# arduino_minimal_1stk.net
KiCad netlist of a schematic drawn in EAGLE
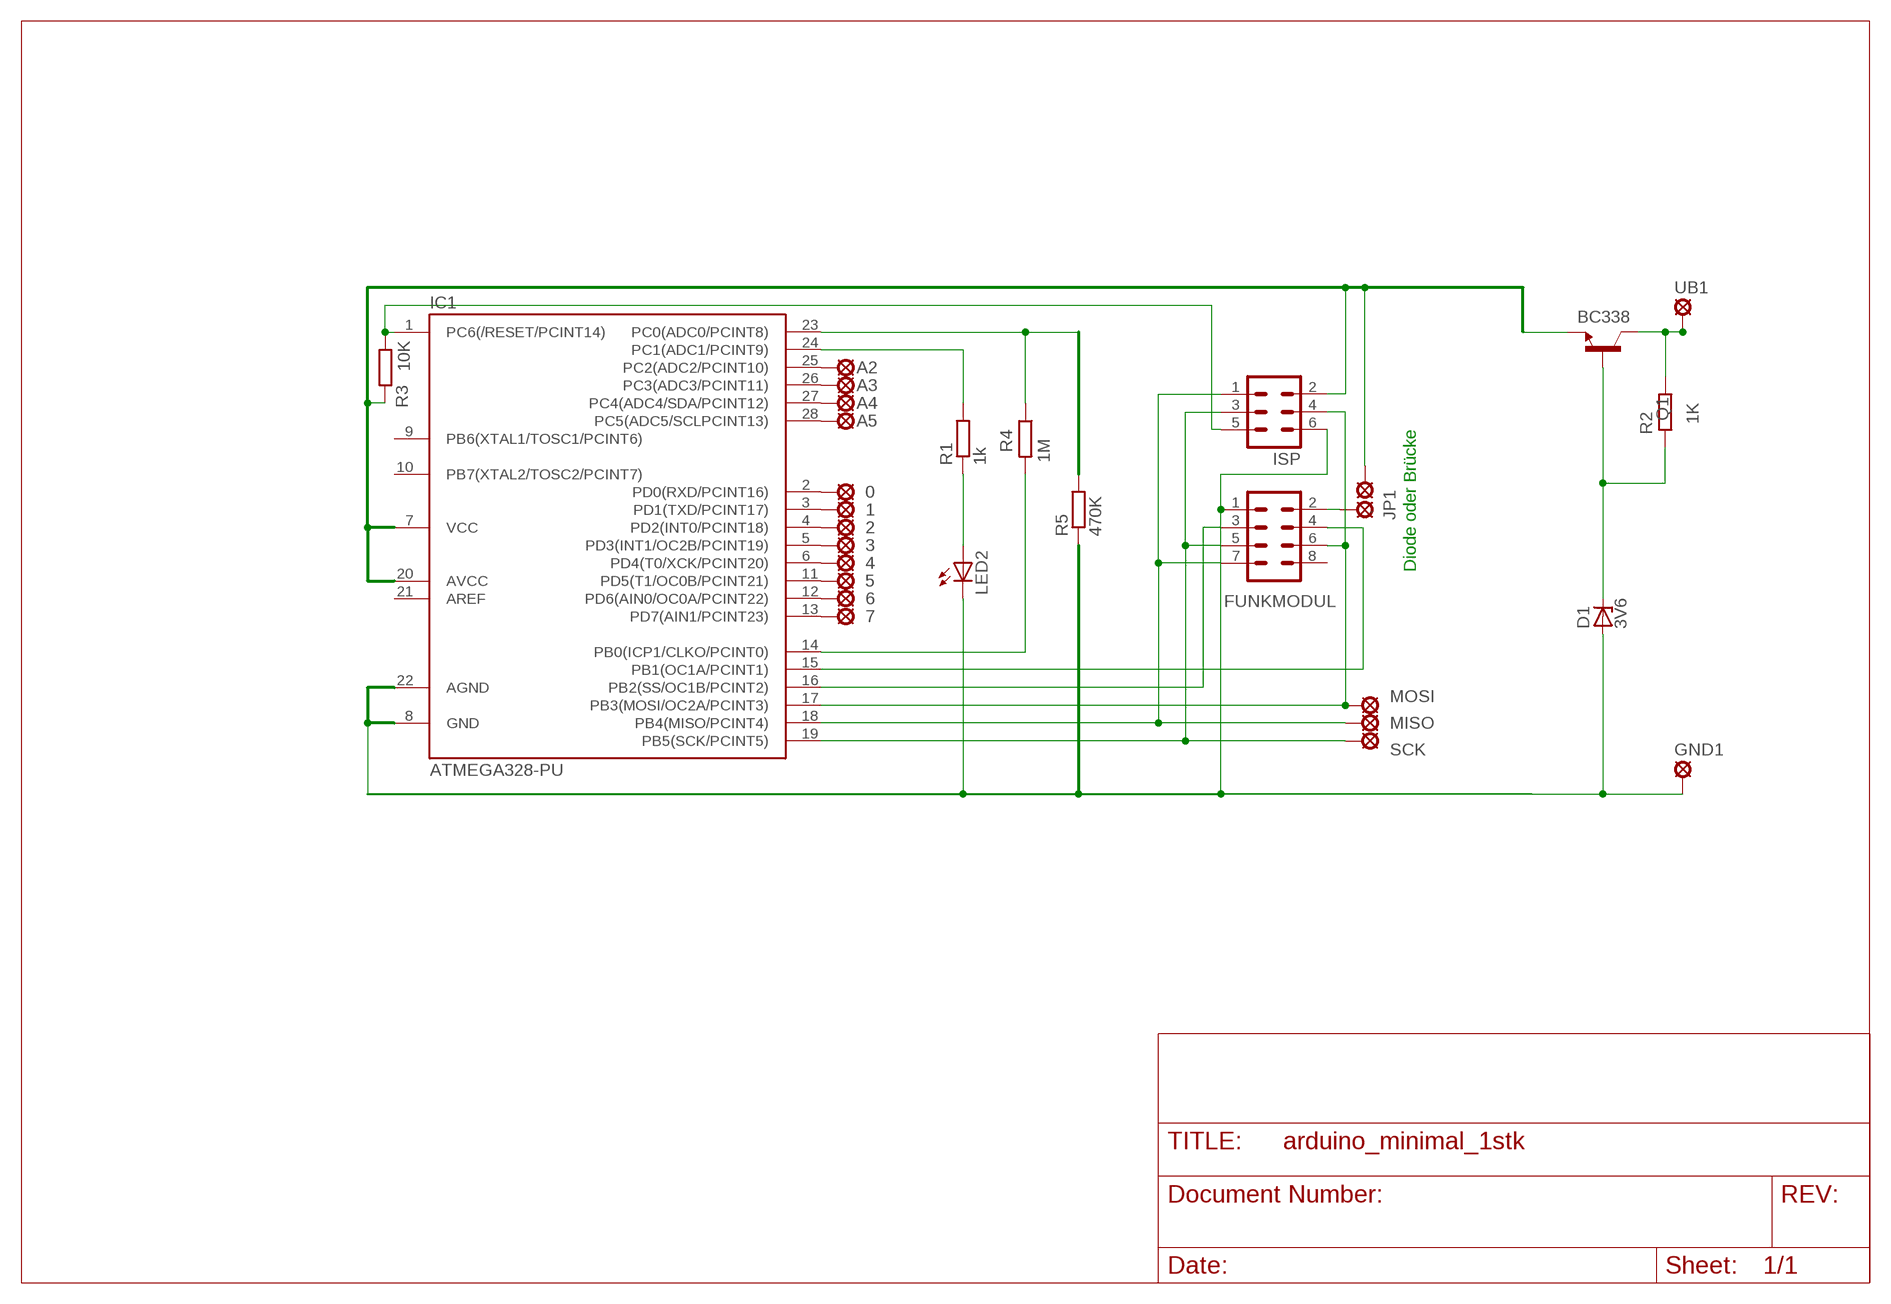
[diagram p0: schematic, sheet 1]

(export (version "E")
  (design (tool "Eeschema 10.0.6"))
  (components
    (comp (ref ".")
      (value "LSP10")
      (footprint "eagle-import:LSP10")
      (libsource (lib "eagle-import") (part "LSP10"))
    )
    (comp (ref "0")
      (value "LSP10")
      (footprint "eagle-import:LSP10")
      (libsource (lib "eagle-import") (part "LSP10"))
    )
    (comp (ref "1")
      (value "LSP10")
      (footprint "eagle-import:LSP10")
      (libsource (lib "eagle-import") (part "LSP10"))
    )
    (comp (ref "2")
      (value "LSP10")
      (footprint "eagle-import:LSP10")
      (libsource (lib "eagle-import") (part "LSP10"))
    )
    (comp (ref "3")
      (value "LSP10")
      (footprint "eagle-import:LSP10")
      (libsource (lib "eagle-import") (part "LSP10"))
    )
    (comp (ref "4")
      (value "LSP10")
      (footprint "eagle-import:LSP10")
      (libsource (lib "eagle-import") (part "LSP10"))
    )
    (comp (ref "5")
      (value "LSP10")
      (footprint "eagle-import:LSP10")
      (libsource (lib "eagle-import") (part "LSP10"))
    )
    (comp (ref "6")
      (value "LSP10")
      (footprint "eagle-import:LSP10")
      (libsource (lib "eagle-import") (part "LSP10"))
    )
    (comp (ref "7")
      (value "LSP10")
      (footprint "eagle-import:LSP10")
      (libsource (lib "eagle-import") (part "LSP10"))
    )
    (comp (ref "A2")
      (value "LSP10")
      (footprint "eagle-import:LSP10")
      (libsource (lib "eagle-import") (part "LSP10"))
    )
    (comp (ref "A3")
      (value "LSP10")
      (footprint "eagle-import:LSP10")
      (libsource (lib "eagle-import") (part "LSP10"))
    )
    (comp (ref "A4")
      (value "LSP10")
      (footprint "eagle-import:LSP10")
      (libsource (lib "eagle-import") (part "LSP10"))
    )
    (comp (ref "A5")
      (value "LSP10")
      (footprint "eagle-import:LSP10")
      (libsource (lib "eagle-import") (part "LSP10"))
    )
    (comp (ref "D1")
      (value "3V6")
      (footprint "eagle-import:DO41Z10")
      (libsource (lib "eagle-import") (part "1N4728"))
    )
    (comp (ref "FUNKMODUL")
      (value "MA04-2")
      (footprint "eagle-import:MA04-2")
      (libsource (lib "eagle-import") (part "MA04-2"))
    )
    (comp (ref "GND1")
      (value "LSP10")
      (footprint "eagle-import:LSP10")
      (libsource (lib "eagle-import") (part "LSP10"))
    )
    (comp (ref "IC1")
      (value "ATMEGA328-PU")
      (footprint "eagle-import:DIL28-3")
      (libsource (lib "eagle-import") (part "MEGA48/88/168-PU"))
    )
    (comp (ref "ISP")
      (value "MA03-2")
      (footprint "eagle-import:MA03-2")
      (libsource (lib "eagle-import") (part "MA03-2"))
    )
    (comp (ref "JP1")
      (value "LSP10")
      (footprint "eagle-import:LSP10")
      (libsource (lib "eagle-import") (part "LSP10"))
    )
    (comp (ref "LED2")
      (value "LED3MM")
      (footprint "eagle-import:LED3MM")
      (libsource (lib "eagle-import") (part "LED3MM"))
    )
    (comp (ref "MISO")
      (value "LSP10")
      (footprint "eagle-import:LSP10")
      (libsource (lib "eagle-import") (part "LSP10"))
    )
    (comp (ref "MOSI")
      (value "LSP10")
      (footprint "eagle-import:LSP10")
      (libsource (lib "eagle-import") (part "LSP10"))
    )
    (comp (ref "Q1")
      (value "BC338")
      (footprint "eagle-import:TO92-EBC")
      (libsource (lib "eagle-import") (part "BC338"))
    )
    (comp (ref "R1")
      (value "1k")
      (footprint "eagle-import:0204_7")
      (libsource (lib "eagle-import") (part "R-EU_0204/7"))
    )
    (comp (ref "R2")
      (value "1K")
      (footprint "eagle-import:0204_7")
      (libsource (lib "eagle-import") (part "R-EU_0204/7"))
    )
    (comp (ref "R3")
      (value "10K")
      (footprint "eagle-import:0204_7")
      (libsource (lib "eagle-import") (part "R-EU_0204/7"))
    )
    (comp (ref "R4")
      (value "1M")
      (footprint "eagle-import:0204_7")
      (libsource (lib "eagle-import") (part "R-EU_0204/7"))
    )
    (comp (ref "R5")
      (value "470K")
      (footprint "eagle-import:0204_7")
      (libsource (lib "eagle-import") (part "R-EU_0204/7"))
    )
    (comp (ref "SCK")
      (value "LSP10")
      (footprint "eagle-import:LSP10")
      (libsource (lib "eagle-import") (part "LSP10"))
    )
    (comp (ref "UB1")
      (value "LSP10")
      (footprint "eagle-import:LSP10")
      (libsource (lib "eagle-import") (part "LSP10"))
    )
  )
  (nets
    (net (code "1") (name "Net-(.-PadMP)") (class "Default")
      (node (ref ".") (pin "MP") (pinfunction "MP_MP") (pintype "passive"))
      (node (ref "FUNKMODUL") (pin "2") (pinfunction "2_2") (pintype "passive"))
    )
    (net (code "2") (name "Net-(D1-PadC)") (class "Default")
      (node (ref "D1") (pin "C") (pinfunction "C_C") (pintype "passive"))
      (node (ref "Q1") (pin "B") (pinfunction "B_B") (pintype "passive"))
      (node (ref "R2") (pin "2") (pinfunction "2_2") (pintype "passive"))
    )
    (net (code "3") (name "Net-(IC1-AGND)") (class "Default")
      (node (ref "D1") (pin "A") (pinfunction "A_A") (pintype "passive"))
      (node (ref "FUNKMODUL") (pin "1") (pinfunction "1_1") (pintype "passive"))
      (node (ref "GND1") (pin "MP") (pinfunction "MP_MP") (pintype "passive"))
      (node (ref "IC1") (pin "22") (pinfunction "AGND_22") (pintype "power_in"))
      (node (ref "IC1") (pin "8") (pinfunction "GND_8") (pintype "power_in"))
      (node (ref "ISP") (pin "6") (pinfunction "6_6") (pintype "passive"))
      (node (ref "LED2") (pin "K") (pinfunction "C_K") (pintype "passive"))
      (node (ref "R5") (pin "1") (pinfunction "1_1") (pintype "passive"))
    )
    (net (code "4") (name "Net-(IC1-AVCC)") (class "Default")
      (node (ref "IC1") (pin "20") (pinfunction "AVCC_20") (pintype "passive"))
      (node (ref "IC1") (pin "7") (pinfunction "VCC_7") (pintype "power_in"))
      (node (ref "ISP") (pin "2") (pinfunction "2_2") (pintype "passive"))
      (node (ref "JP1") (pin "MP") (pinfunction "MP_MP") (pintype "passive"))
      (node (ref "Q1") (pin "E") (pinfunction "E_E") (pintype "passive"))
      (node (ref "R3") (pin "2") (pinfunction "2_2") (pintype "passive"))
    )
    (net (code "5") (name "Net-(IC1-PB0(ICP1{slash}CLKO{slash}PCINT0))") (class "Default")
      (node (ref "IC1") (pin "14") (pinfunction "PB0(ICP1/CLKO/PCINT0)_14") (pintype "bidirectional"))
      (node (ref "R4") (pin "2") (pinfunction "2_2") (pintype "passive"))
    )
    (net (code "6") (name "Net-(IC1-PB1(OC1A{slash}PCINT1))") (class "Default")
      (node (ref "FUNKMODUL") (pin "4") (pinfunction "4_4") (pintype "passive"))
      (node (ref "IC1") (pin "15") (pinfunction "PB1(OC1A/PCINT1)_15") (pintype "bidirectional"))
    )
    (net (code "7") (name "Net-(IC1-PB2(SS{slash}OC1B{slash}PCINT2))") (class "Default")
      (node (ref "FUNKMODUL") (pin "3") (pinfunction "3_3") (pintype "passive"))
      (node (ref "IC1") (pin "16") (pinfunction "PB2(SS/OC1B/PCINT2)_16") (pintype "bidirectional"))
    )
    (net (code "8") (name "Net-(IC1-PB3(MOSI{slash}OC2A{slash}PCINT3))") (class "Default")
      (node (ref "FUNKMODUL") (pin "6") (pinfunction "6_6") (pintype "passive"))
      (node (ref "IC1") (pin "17") (pinfunction "PB3(MOSI/OC2A/PCINT3)_17") (pintype "bidirectional"))
      (node (ref "ISP") (pin "4") (pinfunction "4_4") (pintype "passive"))
      (node (ref "MOSI") (pin "MP") (pinfunction "MP_MP") (pintype "passive"))
    )
    (net (code "9") (name "Net-(IC1-PB4(MISO{slash}PCINT4))") (class "Default")
      (node (ref "FUNKMODUL") (pin "7") (pinfunction "7_7") (pintype "passive"))
      (node (ref "IC1") (pin "18") (pinfunction "PB4(MISO/PCINT4)_18") (pintype "bidirectional"))
      (node (ref "ISP") (pin "1") (pinfunction "1_1") (pintype "passive"))
      (node (ref "MISO") (pin "MP") (pinfunction "MP_MP") (pintype "passive"))
    )
    (net (code "10") (name "Net-(IC1-PB5(SCK{slash}PCINT5))") (class "Default")
      (node (ref "FUNKMODUL") (pin "5") (pinfunction "5_5") (pintype "passive"))
      (node (ref "IC1") (pin "19") (pinfunction "PB5(SCK/PCINT5)_19") (pintype "bidirectional"))
      (node (ref "ISP") (pin "3") (pinfunction "3_3") (pintype "passive"))
      (node (ref "SCK") (pin "MP") (pinfunction "MP_MP") (pintype "passive"))
    )
    (net (code "11") (name "Net-(IC1-PC0(ADC0{slash}PCINT8))") (class "Default")
      (node (ref "IC1") (pin "23") (pinfunction "PC0(ADC0/PCINT8)_23") (pintype "bidirectional"))
      (node (ref "R4") (pin "1") (pinfunction "1_1") (pintype "passive"))
      (node (ref "R5") (pin "2") (pinfunction "2_2") (pintype "passive"))
    )
    (net (code "12") (name "Net-(IC1-PC1(ADC1{slash}PCINT9))") (class "Default")
      (node (ref "IC1") (pin "24") (pinfunction "PC1(ADC1/PCINT9)_24") (pintype "bidirectional"))
      (node (ref "R1") (pin "2") (pinfunction "2_2") (pintype "passive"))
    )
    (net (code "13") (name "Net-(IC1-PC2(ADC2{slash}PCINT10))") (class "Default")
      (node (ref "A2") (pin "MP") (pinfunction "MP_MP") (pintype "passive"))
      (node (ref "IC1") (pin "25") (pinfunction "PC2(ADC2/PCINT10)_25") (pintype "bidirectional"))
    )
    (net (code "14") (name "Net-(IC1-PC3(ADC3{slash}PCINT11))") (class "Default")
      (node (ref "A3") (pin "MP") (pinfunction "MP_MP") (pintype "passive"))
      (node (ref "IC1") (pin "26") (pinfunction "PC3(ADC3/PCINT11)_26") (pintype "bidirectional"))
    )
    (net (code "15") (name "Net-(IC1-PC4(ADC4{slash}SDA{slash}PCINT12))") (class "Default")
      (node (ref "A4") (pin "MP") (pinfunction "MP_MP") (pintype "passive"))
      (node (ref "IC1") (pin "27") (pinfunction "PC4(ADC4/SDA/PCINT12)_27") (pintype "bidirectional"))
    )
    (net (code "16") (name "Net-(IC1-PC5(ADC5{slash}SCLPCINT13))") (class "Default")
      (node (ref "A5") (pin "MP") (pinfunction "MP_MP") (pintype "passive"))
      (node (ref "IC1") (pin "28") (pinfunction "PC5(ADC5/SCLPCINT13)_28") (pintype "bidirectional"))
    )
    (net (code "17") (name "Net-(IC1-PC6({slash}RESET{slash}PCINT14))") (class "Default")
      (node (ref "IC1") (pin "1") (pinfunction "PC6(/RESET/PCINT14)_1") (pintype "bidirectional"))
      (node (ref "ISP") (pin "5") (pinfunction "5_5") (pintype "passive"))
      (node (ref "R3") (pin "1") (pinfunction "1_1") (pintype "passive"))
    )
    (net (code "18") (name "Net-(IC1-PD0(RXD{slash}PCINT16))") (class "Default")
      (node (ref "0") (pin "MP") (pinfunction "MP_MP") (pintype "passive"))
      (node (ref "IC1") (pin "2") (pinfunction "PD0(RXD/PCINT16)_2") (pintype "bidirectional"))
    )
    (net (code "19") (name "Net-(IC1-PD1(TXD{slash}PCINT17))") (class "Default")
      (node (ref "1") (pin "MP") (pinfunction "MP_MP") (pintype "passive"))
      (node (ref "IC1") (pin "3") (pinfunction "PD1(TXD/PCINT17)_3") (pintype "bidirectional"))
    )
    (net (code "20") (name "Net-(IC1-PD2(INT0{slash}PCINT18))") (class "Default")
      (node (ref "2") (pin "MP") (pinfunction "MP_MP") (pintype "passive"))
      (node (ref "IC1") (pin "4") (pinfunction "PD2(INT0/PCINT18)_4") (pintype "bidirectional"))
    )
    (net (code "21") (name "Net-(IC1-PD3(INT1{slash}OC2B{slash}PCINT19))") (class "Default")
      (node (ref "3") (pin "MP") (pinfunction "MP_MP") (pintype "passive"))
      (node (ref "IC1") (pin "5") (pinfunction "PD3(INT1/OC2B/PCINT19)_5") (pintype "bidirectional"))
    )
    (net (code "22") (name "Net-(IC1-PD4(T0{slash}XCK{slash}PCINT20))") (class "Default")
      (node (ref "4") (pin "MP") (pinfunction "MP_MP") (pintype "passive"))
      (node (ref "IC1") (pin "6") (pinfunction "PD4(T0/XCK/PCINT20)_6") (pintype "bidirectional"))
    )
    (net (code "23") (name "Net-(IC1-PD5(T1{slash}OC0B{slash}PCINT21))") (class "Default")
      (node (ref "5") (pin "MP") (pinfunction "MP_MP") (pintype "passive"))
      (node (ref "IC1") (pin "11") (pinfunction "PD5(T1/OC0B/PCINT21)_11") (pintype "bidirectional"))
    )
    (net (code "24") (name "Net-(IC1-PD6(AIN0{slash}OC0A{slash}PCINT22))") (class "Default")
      (node (ref "6") (pin "MP") (pinfunction "MP_MP") (pintype "passive"))
      (node (ref "IC1") (pin "12") (pinfunction "PD6(AIN0/OC0A/PCINT22)_12") (pintype "bidirectional"))
    )
    (net (code "25") (name "Net-(IC1-PD7(AIN1{slash}PCINT23))") (class "Default")
      (node (ref "7") (pin "MP") (pinfunction "MP_MP") (pintype "passive"))
      (node (ref "IC1") (pin "13") (pinfunction "PD7(AIN1/PCINT23)_13") (pintype "bidirectional"))
    )
    (net (code "26") (name "Net-(LED2-PadA)") (class "Default")
      (node (ref "LED2") (pin "A") (pinfunction "A_A") (pintype "passive"))
      (node (ref "R1") (pin "1") (pinfunction "1_1") (pintype "passive"))
    )
    (net (code "27") (name "Net-(Q1-PadC)") (class "Default")
      (node (ref "Q1") (pin "C") (pinfunction "C_C") (pintype "passive"))
      (node (ref "R2") (pin "1") (pinfunction "1_1") (pintype "passive"))
      (node (ref "UB1") (pin "MP") (pinfunction "MP_MP") (pintype "passive"))
    )
    (net (code "28") (name "unconnected-(FUNKMODUL-Pad8)") (class "Default")
      (node (ref "FUNKMODUL") (pin "8") (pinfunction "8_8") (pintype "passive"))
    )
    (net (code "29") (name "unconnected-(IC1-AREF-Pad21)") (class "Default")
      (node (ref "IC1") (pin "21") (pinfunction "AREF_21") (pintype "passive"))
    )
    (net (code "30") (name "unconnected-(IC1-PB6(XTAL1{slash}TOSC1{slash}PCINT6)-Pad9)") (class "Default")
      (node (ref "IC1") (pin "9") (pinfunction "PB6(XTAL1/TOSC1/PCINT6)_9") (pintype "bidirectional"))
    )
    (net (code "31") (name "unconnected-(IC1-PB7(XTAL2{slash}TOSC2{slash}PCINT7)-Pad10)") (class "Default")
      (node (ref "IC1") (pin "10") (pinfunction "PB7(XTAL2/TOSC2/PCINT7)_10") (pintype "bidirectional"))
    )
  )
)
